# Board.net
KiCad netlist of a schematic drawn in EAGLE
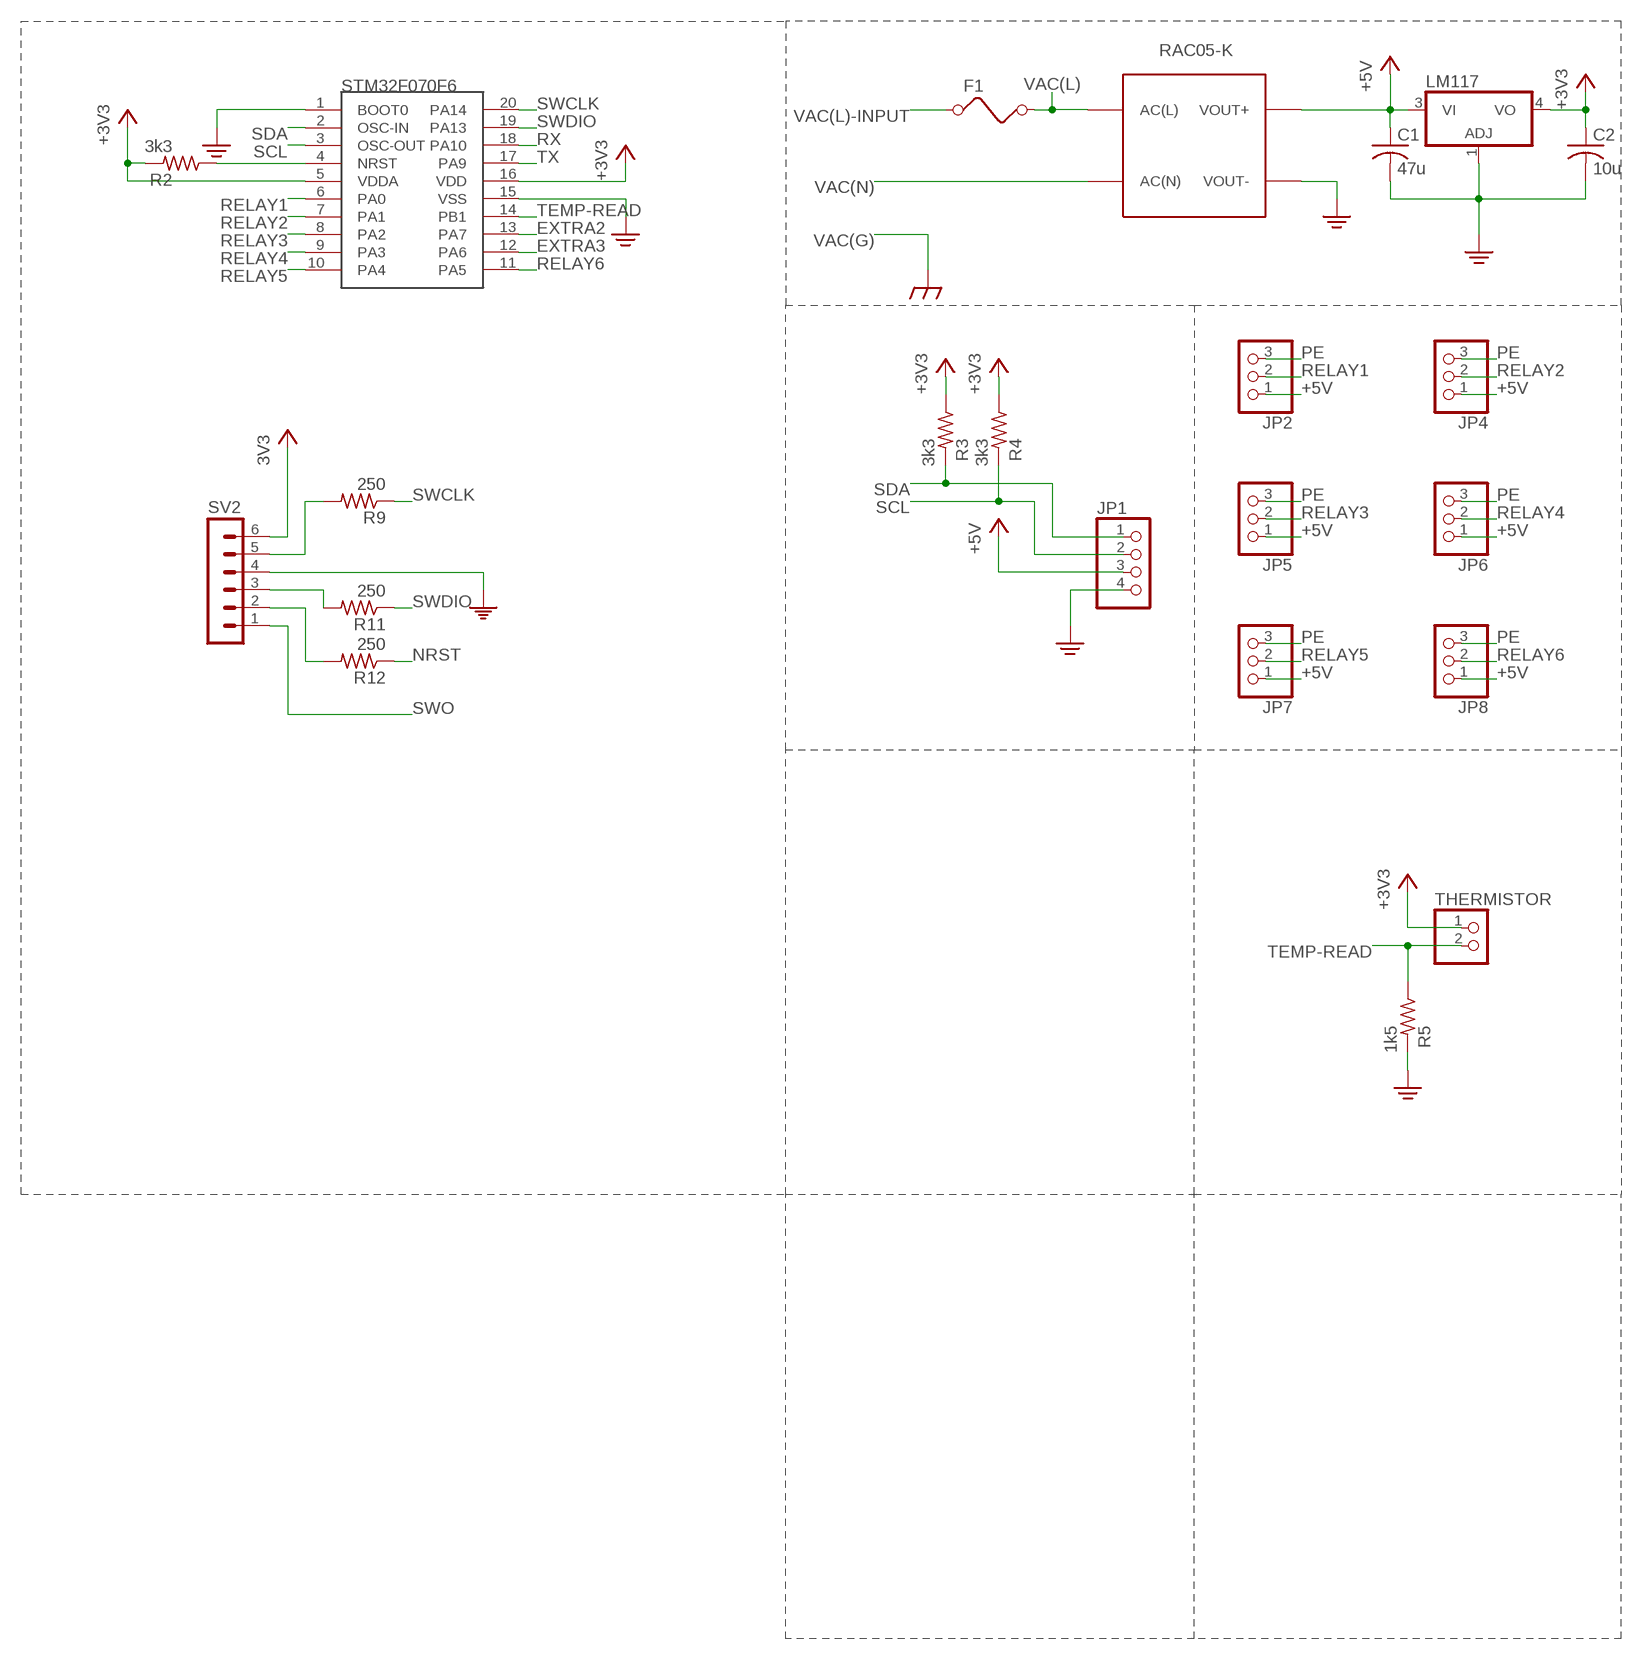
[diagram p0: schematic, sheet 1]

(export (version "E")
  (design (tool "Eeschema 10.0.6"))
  (components
    (comp (ref "C1")
      (value "47u")
      (footprint "eagle-import:C0603")
      (libsource (lib "eagle-import") (part "C-USC0603"))
    )
    (comp (ref "C2")
      (value "10u")
      (footprint "eagle-import:C0603")
      (libsource (lib "eagle-import") (part "C-USC0603"))
    )
    (comp (ref "F1")
      (value "FUSE")
      (footprint "eagle-import:FUSE")
      (libsource (lib "eagle-import") (part "FUSE"))
    )
    (comp (ref "JP1")
      (value "PINHD-1X4")
      (footprint "eagle-import:1X04")
      (libsource (lib "eagle-import") (part "PINHD-1X4"))
    )
    (comp (ref "JP2")
      (value "PINHD-1X3")
      (footprint "eagle-import:1X03")
      (libsource (lib "eagle-import") (part "PINHD-1X3"))
    )
    (comp (ref "JP4")
      (value "PINHD-1X3")
      (footprint "eagle-import:1X03")
      (libsource (lib "eagle-import") (part "PINHD-1X3"))
    )
    (comp (ref "JP5")
      (value "PINHD-1X3")
      (footprint "eagle-import:1X03")
      (libsource (lib "eagle-import") (part "PINHD-1X3"))
    )
    (comp (ref "JP6")
      (value "PINHD-1X3")
      (footprint "eagle-import:1X03")
      (libsource (lib "eagle-import") (part "PINHD-1X3"))
    )
    (comp (ref "JP7")
      (value "PINHD-1X3")
      (footprint "eagle-import:1X03")
      (libsource (lib "eagle-import") (part "PINHD-1X3"))
    )
    (comp (ref "JP8")
      (value "PINHD-1X3")
      (footprint "eagle-import:1X03")
      (libsource (lib "eagle-import") (part "PINHD-1X3"))
    )
    (comp (ref "LM117")
      (value "317EMP")
      (footprint "eagle-import:SOT223")
      (libsource (lib "eagle-import") (part "317EMP"))
    )
    (comp (ref "R2")
      (value "3k3")
      (footprint "eagle-import:R0603")
      (libsource (lib "eagle-import") (part "R-US_R0603"))
    )
    (comp (ref "R3")
      (value "3k3")
      (footprint "eagle-import:R0603")
      (libsource (lib "eagle-import") (part "R-US_R0603"))
    )
    (comp (ref "R4")
      (value "3k3")
      (footprint "eagle-import:R0603")
      (libsource (lib "eagle-import") (part "R-US_R0603"))
    )
    (comp (ref "R5")
      (value "1k5")
      (footprint "eagle-import:R0603")
      (libsource (lib "eagle-import") (part "R-US_R0603"))
    )
    (comp (ref "R9")
      (value "250")
      (footprint "eagle-import:R0603")
      (libsource (lib "eagle-import") (part "R-US_R0603"))
    )
    (comp (ref "R11")
      (value "250")
      (footprint "eagle-import:R0603")
      (libsource (lib "eagle-import") (part "R-US_R0603"))
    )
    (comp (ref "R12")
      (value "250")
      (footprint "eagle-import:R0603")
      (libsource (lib "eagle-import") (part "R-US_R0603"))
    )
    (comp (ref "RAC05-K")
      (value "AC/DC-CONVERTER")
      (footprint "eagle-import:AC_DC-CONVERTER")
      (libsource (lib "eagle-import") (part "AC/DC-CONVERTER"))
    )
    (comp (ref "STM32F070F6")
      (value "STM32F07")
      (footprint "eagle-import:TSSOP20")
      (libsource (lib "eagle-import") (part "STM32F07"))
    )
    (comp (ref "SV2")
      (value "MA06-1")
      (footprint "eagle-import:MA06-1")
      (libsource (lib "eagle-import") (part "MA06-1"))
    )
    (comp (ref "THERMISTOR")
      (value "PINHD-1X2")
      (footprint "eagle-import:1X02")
      (libsource (lib "eagle-import") (part "PINHD-1X2"))
    )
  )
  (nets
    (net (code "1") (name "+3V3") (class "Default")
      (node (ref "C2") (pin "1") (pinfunction "1_1") (pintype "passive"))
      (node (ref "LM117") (pin "4") (pinfunction "VO_4") (pintype "passive"))
      (node (ref "R2") (pin "2") (pinfunction "2_2") (pintype "passive"))
      (node (ref "R3") (pin "1") (pinfunction "1_1") (pintype "passive"))
      (node (ref "R4") (pin "1") (pinfunction "1_1") (pintype "passive"))
      (node (ref "STM32F070F6") (pin "16") (pinfunction "VDD_16") (pintype "bidirectional"))
      (node (ref "STM32F070F6") (pin "5") (pinfunction "VDDA_5") (pintype "bidirectional"))
      (node (ref "SV2") (pin "6") (pinfunction "6_6") (pintype "passive"))
      (node (ref "THERMISTOR") (pin "1") (pinfunction "1_1") (pintype "passive"))
    )
    (net (code "2") (name "+5V") (class "Default")
      (node (ref "C1") (pin "1") (pinfunction "1_1") (pintype "passive"))
      (node (ref "JP1") (pin "3") (pinfunction "3_3") (pintype "passive"))
      (node (ref "JP2") (pin "1") (pinfunction "1_1") (pintype "passive"))
      (node (ref "JP4") (pin "1") (pinfunction "1_1") (pintype "passive"))
      (node (ref "JP5") (pin "1") (pinfunction "1_1") (pintype "passive"))
      (node (ref "JP6") (pin "1") (pinfunction "1_1") (pintype "passive"))
      (node (ref "JP7") (pin "1") (pinfunction "1_1") (pintype "passive"))
      (node (ref "JP8") (pin "1") (pinfunction "1_1") (pintype "passive"))
      (node (ref "LM117") (pin "3") (pinfunction "VI_3") (pintype "input"))
      (node (ref "RAC05-K") (pin "+5V") (pinfunction "VOUT+_+5V") (pintype "bidirectional"))
    )
    (net (code "3") (name "/EXTRA2") (class "Default")
      (node (ref "STM32F070F6") (pin "13") (pinfunction "PA7_13") (pintype "bidirectional"))
    )
    (net (code "4") (name "/EXTRA3") (class "Default")
      (node (ref "STM32F070F6") (pin "12") (pinfunction "PA6_12") (pintype "bidirectional"))
    )
    (net (code "5") (name "/NRST") (class "Default")
      (node (ref "R12") (pin "1") (pinfunction "1_1") (pintype "passive"))
      (node (ref "R2") (pin "1") (pinfunction "1_1") (pintype "passive"))
      (node (ref "STM32F070F6") (pin "4") (pinfunction "NRST_4") (pintype "bidirectional"))
    )
    (net (code "6") (name "/RELAY1") (class "Default")
      (node (ref "JP2") (pin "2") (pinfunction "2_2") (pintype "passive"))
      (node (ref "STM32F070F6") (pin "6") (pinfunction "PA0_6") (pintype "bidirectional"))
    )
    (net (code "7") (name "/RELAY2") (class "Default")
      (node (ref "JP4") (pin "2") (pinfunction "2_2") (pintype "passive"))
      (node (ref "STM32F070F6") (pin "7") (pinfunction "PA1_7") (pintype "bidirectional"))
    )
    (net (code "8") (name "/RELAY3") (class "Default")
      (node (ref "JP5") (pin "2") (pinfunction "2_2") (pintype "passive"))
      (node (ref "STM32F070F6") (pin "8") (pinfunction "PA2_8") (pintype "bidirectional"))
    )
    (net (code "9") (name "/RELAY4") (class "Default")
      (node (ref "JP6") (pin "2") (pinfunction "2_2") (pintype "passive"))
      (node (ref "STM32F070F6") (pin "9") (pinfunction "PA3_9") (pintype "bidirectional"))
    )
    (net (code "10") (name "/RELAY5") (class "Default")
      (node (ref "JP7") (pin "2") (pinfunction "2_2") (pintype "passive"))
      (node (ref "STM32F070F6") (pin "10") (pinfunction "PA4_10") (pintype "bidirectional"))
    )
    (net (code "11") (name "/RELAY6") (class "Default")
      (node (ref "JP8") (pin "2") (pinfunction "2_2") (pintype "passive"))
      (node (ref "STM32F070F6") (pin "11") (pinfunction "PA5_11") (pintype "bidirectional"))
    )
    (net (code "12") (name "/RX") (class "Default")
      (node (ref "STM32F070F6") (pin "18") (pinfunction "PA10_18") (pintype "bidirectional"))
    )
    (net (code "13") (name "/SCL") (class "Default")
      (node (ref "JP1") (pin "2") (pinfunction "2_2") (pintype "passive"))
      (node (ref "R4") (pin "2") (pinfunction "2_2") (pintype "passive"))
      (node (ref "STM32F070F6") (pin "3") (pinfunction "OSC-OUT_3") (pintype "bidirectional"))
    )
    (net (code "14") (name "/SDA") (class "Default")
      (node (ref "JP1") (pin "1") (pinfunction "1_1") (pintype "passive"))
      (node (ref "R3") (pin "2") (pinfunction "2_2") (pintype "passive"))
      (node (ref "STM32F070F6") (pin "2") (pinfunction "OSC-IN_2") (pintype "bidirectional"))
    )
    (net (code "15") (name "/SWCLK") (class "Default")
      (node (ref "R9") (pin "1") (pinfunction "1_1") (pintype "passive"))
      (node (ref "STM32F070F6") (pin "20") (pinfunction "PA14_20") (pintype "bidirectional"))
    )
    (net (code "16") (name "/SWDIO") (class "Default")
      (node (ref "R11") (pin "1") (pinfunction "1_1") (pintype "passive"))
      (node (ref "STM32F070F6") (pin "19") (pinfunction "PA13_19") (pintype "bidirectional"))
    )
    (net (code "17") (name "/SWO") (class "Default")
      (node (ref "SV2") (pin "1") (pinfunction "1_1") (pintype "passive"))
    )
    (net (code "18") (name "/TEMP-READ") (class "Default")
      (node (ref "R5") (pin "1") (pinfunction "1_1") (pintype "passive"))
      (node (ref "STM32F070F6") (pin "14") (pinfunction "PB1_14") (pintype "bidirectional"))
      (node (ref "THERMISTOR") (pin "2") (pinfunction "2_2") (pintype "passive"))
    )
    (net (code "19") (name "/TX") (class "Default")
      (node (ref "STM32F070F6") (pin "17") (pinfunction "PA9_17") (pintype "bidirectional"))
    )
    (net (code "20") (name "/VAC(L)") (class "Default")
      (node (ref "F1") (pin "2") (pinfunction "2_2") (pintype "passive"))
      (node (ref "RAC05-K") (pin "L") (pinfunction "AC(L)_L") (pintype "bidirectional"))
    )
    (net (code "21") (name "/VAC(L)-INPUT") (class "Default")
      (node (ref "F1") (pin "1") (pinfunction "1_1") (pintype "passive"))
    )
    (net (code "22") (name "/VAC(N)") (class "Default")
      (node (ref "RAC05-K") (pin "N") (pinfunction "AC(N)_N") (pintype "bidirectional"))
    )
    (net (code "23") (name "GND") (class "Default")
      (node (ref "SV2") (pin "4") (pinfunction "4_4") (pintype "passive"))
    )
    (net (code "24") (name "Net-(R9-Pad2)") (class "Default")
      (node (ref "R9") (pin "2") (pinfunction "2_2") (pintype "passive"))
      (node (ref "SV2") (pin "5") (pinfunction "5_5") (pintype "passive"))
    )
    (net (code "25") (name "Net-(R11-Pad2)") (class "Default")
      (node (ref "R11") (pin "2") (pinfunction "2_2") (pintype "passive"))
      (node (ref "SV2") (pin "3") (pinfunction "3_3") (pintype "passive"))
    )
    (net (code "26") (name "Net-(R12-Pad2)") (class "Default")
      (node (ref "R12") (pin "2") (pinfunction "2_2") (pintype "passive"))
      (node (ref "SV2") (pin "2") (pinfunction "2_2") (pintype "passive"))
    )
    (net (code "27") (name "PE") (class "Default")
      (node (ref "C1") (pin "2") (pinfunction "2_2") (pintype "passive"))
      (node (ref "C2") (pin "2") (pinfunction "2_2") (pintype "passive"))
      (node (ref "JP1") (pin "4") (pinfunction "4_4") (pintype "passive"))
      (node (ref "JP2") (pin "3") (pinfunction "3_3") (pintype "passive"))
      (node (ref "JP4") (pin "3") (pinfunction "3_3") (pintype "passive"))
      (node (ref "JP5") (pin "3") (pinfunction "3_3") (pintype "passive"))
      (node (ref "JP6") (pin "3") (pinfunction "3_3") (pintype "passive"))
      (node (ref "JP7") (pin "3") (pinfunction "3_3") (pintype "passive"))
      (node (ref "JP8") (pin "3") (pinfunction "3_3") (pintype "passive"))
      (node (ref "LM117") (pin "1") (pinfunction "ADJ_1") (pintype "input"))
      (node (ref "R5") (pin "2") (pinfunction "2_2") (pintype "passive"))
      (node (ref "RAC05-K") (pin "GND") (pinfunction "VOUT-_GND") (pintype "bidirectional"))
      (node (ref "STM32F070F6") (pin "1") (pinfunction "BOOT0_1") (pintype "bidirectional"))
      (node (ref "STM32F070F6") (pin "15") (pinfunction "VSS_15") (pintype "bidirectional"))
    )
  )
)
